# 06-Si5341_PLL.net
KiCad netlist of a schematic drawn in Altium Designer
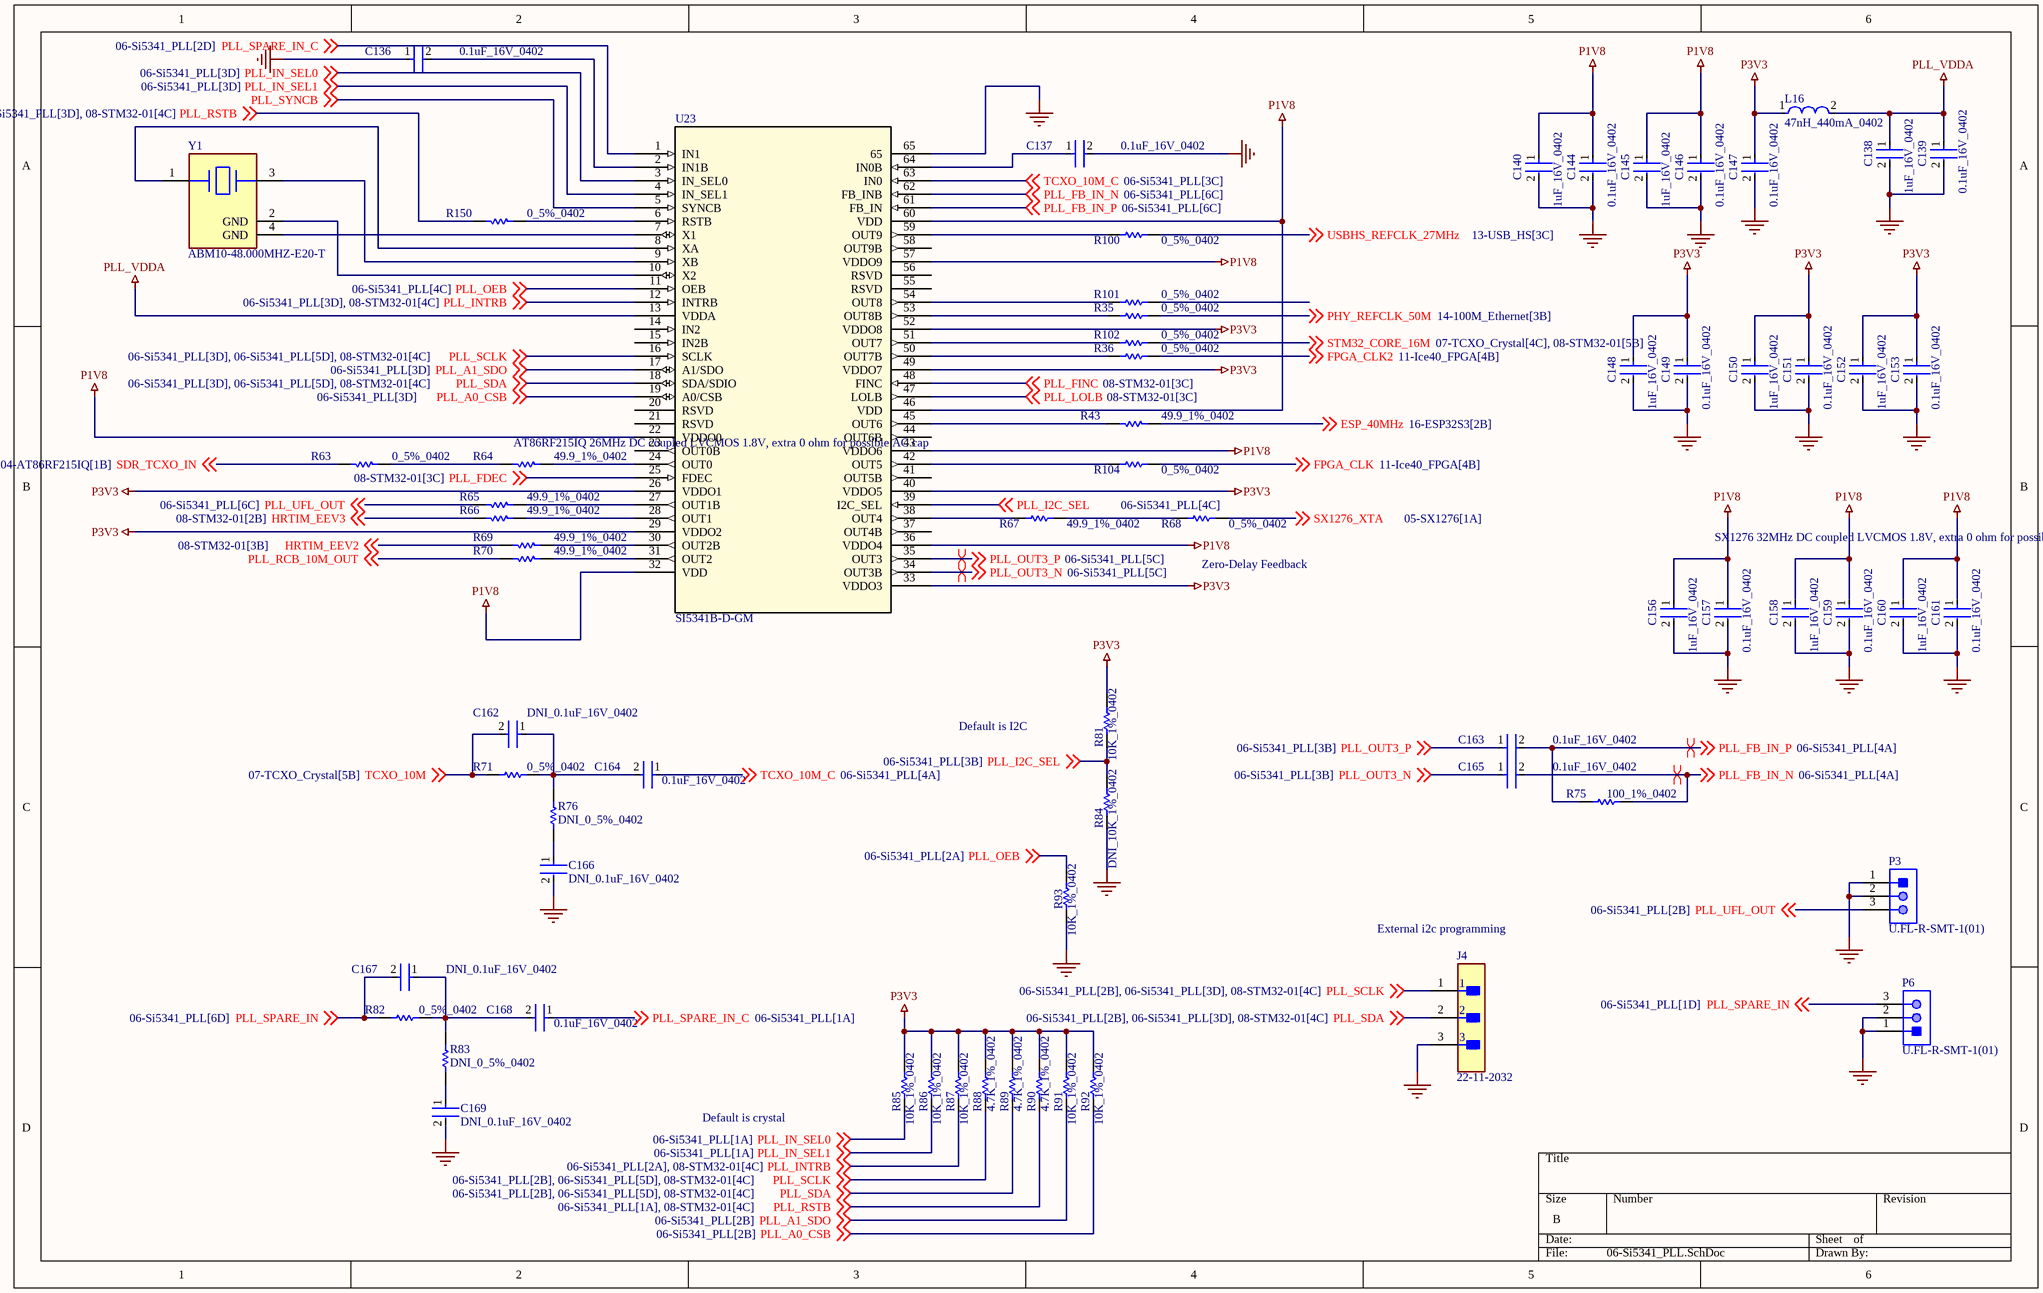
[diagram p0: 06-Si5341_PLL.SchDoc]

(export (version "E")
  (design (tool "Eeschema 10.0.6"))
  (components
    (comp (ref "C136")
      (value "0.1uF_16V_0402")
      (footprint "FP-C0402-BB-MFG")
      (description "CAP CER 0.1UF 16V 5% X7R 0402")
      (fields
        (field (name "MANUFACTURER") "Kemet")
        (field (name "MANUFACTURER PART NUMBER") "C0402C104J4RACTU")
      )
      (libsource (lib "Altium Content Vault") (part "b4654b650e69147ec39a6b967a45e02"))
    )
    (comp (ref "C137")
      (value "0.1uF_16V_0402")
      (footprint "FP-C0402-BB-MFG")
      (description "CAP CER 0.1UF 16V 5% X7R 0402")
      (fields
        (field (name "MANUFACTURER") "Kemet")
        (field (name "MANUFACTURER PART NUMBER") "C0402C104J4RACTU")
      )
      (libsource (lib "Altium Content Vault") (part "b4654b650e69147ec39a6b967a45e02"))
    )
    (comp (ref "C138")
      (value "1uF_16V_0402")
      (footprint "FP-0402-L_1_0_0_05-W_0_5-IPC_A")
      (description "None")
      (fields (field (name "TOLERANCE") "10%"))
      (libsource (lib "Altium Content Vault") (part "b4654b650e69147ec39a6b967a45e02"))
    )
    (comp (ref "C139")
      (value "0.1uF_16V_0402")
      (footprint "FP-C0402-BB-MFG")
      (description "CAP CER 0.1UF 16V 5% X7R 0402")
      (fields
        (field (name "MANUFACTURER") "Kemet")
        (field (name "MANUFACTURER PART NUMBER") "C0402C104J4RACTU")
      )
      (libsource (lib "Altium Content Vault") (part "b4654b650e69147ec39a6b967a45e02"))
    )
    (comp (ref "C140")
      (value "1uF_16V_0402")
      (footprint "FP-0402-L_1_0_0_05-W_0_5-IPC_A")
      (description "None")
      (fields (field (name "TOLERANCE") "10%"))
      (libsource (lib "Altium Content Vault") (part "b4654b650e69147ec39a6b967a45e02"))
    )
    (comp (ref "C144")
      (value "0.1uF_16V_0402")
      (footprint "FP-C0402-BB-MFG")
      (description "CAP CER 0.1UF 16V 5% X7R 0402")
      (fields
        (field (name "MANUFACTURER") "Kemet")
        (field (name "MANUFACTURER PART NUMBER") "C0402C104J4RACTU")
      )
      (libsource (lib "Altium Content Vault") (part "b4654b650e69147ec39a6b967a45e02"))
    )
    (comp (ref "C145")
      (value "1uF_16V_0402")
      (footprint "FP-0402-L_1_0_0_05-W_0_5-IPC_A")
      (description "None")
      (fields (field (name "TOLERANCE") "10%"))
      (libsource (lib "Altium Content Vault") (part "b4654b650e69147ec39a6b967a45e02"))
    )
    (comp (ref "C146")
      (value "0.1uF_16V_0402")
      (footprint "FP-C0402-BB-MFG")
      (description "CAP CER 0.1UF 16V 5% X7R 0402")
      (fields
        (field (name "MANUFACTURER") "Kemet")
        (field (name "MANUFACTURER PART NUMBER") "C0402C104J4RACTU")
      )
      (libsource (lib "Altium Content Vault") (part "b4654b650e69147ec39a6b967a45e02"))
    )
    (comp (ref "C147")
      (value "0.1uF_16V_0402")
      (footprint "FP-C0402-BB-MFG")
      (description "CAP CER 0.1UF 16V 5% X7R 0402")
      (fields
        (field (name "MANUFACTURER") "Kemet")
        (field (name "MANUFACTURER PART NUMBER") "C0402C104J4RACTU")
      )
      (libsource (lib "Altium Content Vault") (part "b4654b650e69147ec39a6b967a45e02"))
    )
    (comp (ref "C148")
      (value "1uF_16V_0402")
      (footprint "FP-0402-L_1_0_0_05-W_0_5-IPC_A")
      (description "None")
      (fields (field (name "TOLERANCE") "10%"))
      (libsource (lib "Altium Content Vault") (part "b4654b650e69147ec39a6b967a45e02"))
    )
    (comp (ref "C149")
      (value "0.1uF_16V_0402")
      (footprint "FP-C0402-BB-MFG")
      (description "CAP CER 0.1UF 16V 5% X7R 0402")
      (fields
        (field (name "MANUFACTURER") "Kemet")
        (field (name "MANUFACTURER PART NUMBER") "C0402C104J4RACTU")
      )
      (libsource (lib "Altium Content Vault") (part "b4654b650e69147ec39a6b967a45e02"))
    )
    (comp (ref "C150")
      (value "1uF_16V_0402")
      (footprint "FP-0402-L_1_0_0_05-W_0_5-IPC_A")
      (description "None")
      (fields (field (name "TOLERANCE") "10%"))
      (libsource (lib "Altium Content Vault") (part "b4654b650e69147ec39a6b967a45e02"))
    )
    (comp (ref "C151")
      (value "0.1uF_16V_0402")
      (footprint "FP-C0402-BB-MFG")
      (description "CAP CER 0.1UF 16V 5% X7R 0402")
      (fields
        (field (name "MANUFACTURER") "Kemet")
        (field (name "MANUFACTURER PART NUMBER") "C0402C104J4RACTU")
      )
      (libsource (lib "Altium Content Vault") (part "b4654b650e69147ec39a6b967a45e02"))
    )
    (comp (ref "C152")
      (value "1uF_16V_0402")
      (footprint "FP-0402-L_1_0_0_05-W_0_5-IPC_A")
      (description "None")
      (fields (field (name "TOLERANCE") "10%"))
      (libsource (lib "Altium Content Vault") (part "b4654b650e69147ec39a6b967a45e02"))
    )
    (comp (ref "C153")
      (value "0.1uF_16V_0402")
      (footprint "FP-C0402-BB-MFG")
      (description "CAP CER 0.1UF 16V 5% X7R 0402")
      (fields
        (field (name "MANUFACTURER") "Kemet")
        (field (name "MANUFACTURER PART NUMBER") "C0402C104J4RACTU")
      )
      (libsource (lib "Altium Content Vault") (part "b4654b650e69147ec39a6b967a45e02"))
    )
    (comp (ref "C156")
      (value "1uF_16V_0402")
      (footprint "FP-0402-L_1_0_0_05-W_0_5-IPC_A")
      (description "None")
      (fields (field (name "TOLERANCE") "10%"))
      (libsource (lib "Altium Content Vault") (part "b4654b650e69147ec39a6b967a45e02"))
    )
    (comp (ref "C157")
      (value "0.1uF_16V_0402")
      (footprint "FP-C0402-BB-MFG")
      (description "CAP CER 0.1UF 16V 5% X7R 0402")
      (fields
        (field (name "MANUFACTURER") "Kemet")
        (field (name "MANUFACTURER PART NUMBER") "C0402C104J4RACTU")
      )
      (libsource (lib "Altium Content Vault") (part "b4654b650e69147ec39a6b967a45e02"))
    )
    (comp (ref "C158")
      (value "1uF_16V_0402")
      (footprint "FP-0402-L_1_0_0_05-W_0_5-IPC_A")
      (description "None")
      (fields (field (name "TOLERANCE") "10%"))
      (libsource (lib "Altium Content Vault") (part "b4654b650e69147ec39a6b967a45e02"))
    )
    (comp (ref "C159")
      (value "0.1uF_16V_0402")
      (footprint "FP-C0402-BB-MFG")
      (description "CAP CER 0.1UF 16V 5% X7R 0402")
      (fields
        (field (name "MANUFACTURER") "Kemet")
        (field (name "MANUFACTURER PART NUMBER") "C0402C104J4RACTU")
      )
      (libsource (lib "Altium Content Vault") (part "b4654b650e69147ec39a6b967a45e02"))
    )
    (comp (ref "C160")
      (value "1uF_16V_0402")
      (footprint "FP-0402-L_1_0_0_05-W_0_5-IPC_A")
      (description "None")
      (fields (field (name "TOLERANCE") "10%"))
      (libsource (lib "Altium Content Vault") (part "b4654b650e69147ec39a6b967a45e02"))
    )
    (comp (ref "C161")
      (value "0.1uF_16V_0402")
      (footprint "FP-C0402-BB-MFG")
      (description "CAP CER 0.1UF 16V 5% X7R 0402")
      (fields
        (field (name "MANUFACTURER") "Kemet")
        (field (name "MANUFACTURER PART NUMBER") "C0402C104J4RACTU")
      )
      (libsource (lib "Altium Content Vault") (part "b4654b650e69147ec39a6b967a45e02"))
    )
    (comp (ref "C162")
      (value "DNI_0.1uF_16V_0402")
      (footprint "FP-C0402-BB-MFG")
      (description "CAP CER 0.1UF 16V 5% X7R 0402")
      (fields
        (field (name "MANUFACTURER") "Kemet")
        (field (name "MANUFACTURER PART NUMBER") "C0402C104J4RACTU")
      )
      (libsource (lib "Altium Content Vault") (part "b4654b650e69147ec39a6b967a45e02"))
    )
    (comp (ref "C163")
      (value "0.1uF_16V_0402")
      (footprint "FP-C0402-BB-MFG")
      (description "CAP CER 0.1UF 16V 5% X7R 0402")
      (fields
        (field (name "MANUFACTURER") "Kemet")
        (field (name "MANUFACTURER PART NUMBER") "C0402C104J4RACTU")
      )
      (libsource (lib "Altium Content Vault") (part "b4654b650e69147ec39a6b967a45e02"))
    )
    (comp (ref "C164")
      (value "0.1uF_16V_0402")
      (footprint "FP-C0402-BB-MFG")
      (description "CAP CER 0.1UF 16V 5% X7R 0402")
      (fields
        (field (name "MANUFACTURER") "Kemet")
        (field (name "MANUFACTURER PART NUMBER") "C0402C104J4RACTU")
      )
      (libsource (lib "Altium Content Vault") (part "b4654b650e69147ec39a6b967a45e02"))
    )
    (comp (ref "C165")
      (value "0.1uF_16V_0402")
      (footprint "FP-C0402-BB-MFG")
      (description "CAP CER 0.1UF 16V 5% X7R 0402")
      (fields
        (field (name "MANUFACTURER") "Kemet")
        (field (name "MANUFACTURER PART NUMBER") "C0402C104J4RACTU")
      )
      (libsource (lib "Altium Content Vault") (part "b4654b650e69147ec39a6b967a45e02"))
    )
    (comp (ref "C166")
      (value "DNI_0.1uF_16V_0402")
      (footprint "FP-C0402-BB-MFG")
      (description "CAP CER 0.1UF 16V 5% X7R 0402")
      (fields
        (field (name "MANUFACTURER") "Kemet")
        (field (name "MANUFACTURER PART NUMBER") "C0402C104J4RACTU")
      )
      (libsource (lib "Altium Content Vault") (part "b4654b650e69147ec39a6b967a45e02"))
    )
    (comp (ref "C167")
      (value "DNI_0.1uF_16V_0402")
      (footprint "FP-C0402-BB-MFG")
      (description "CAP CER 0.1UF 16V 5% X7R 0402")
      (fields
        (field (name "MANUFACTURER") "Kemet")
        (field (name "MANUFACTURER PART NUMBER") "C0402C104J4RACTU")
      )
      (libsource (lib "Altium Content Vault") (part "b4654b650e69147ec39a6b967a45e02"))
    )
    (comp (ref "C168")
      (value "0.1uF_16V_0402")
      (footprint "FP-C0402-BB-MFG")
      (description "CAP CER 0.1UF 16V 5% X7R 0402")
      (fields
        (field (name "MANUFACTURER") "Kemet")
        (field (name "MANUFACTURER PART NUMBER") "C0402C104J4RACTU")
      )
      (libsource (lib "Altium Content Vault") (part "b4654b650e69147ec39a6b967a45e02"))
    )
    (comp (ref "C169")
      (value "DNI_0.1uF_16V_0402")
      (footprint "FP-C0402-BB-MFG")
      (description "CAP CER 0.1UF 16V 5% X7R 0402")
      (fields
        (field (name "MANUFACTURER") "Kemet")
        (field (name "MANUFACTURER PART NUMBER") "C0402C104J4RACTU")
      )
      (libsource (lib "Altium Content Vault") (part "b4654b650e69147ec39a6b967a45e02"))
    )
    (comp (ref "J4")
      (value "22-11-2032")
      (footprint "FP-22-11-2032-MFG")
      (description "CONN HEADER VERT 3POS 2.54MM")
      (fields
        (field (name "MANUFACTURER") "Molex")
        (field (name "OCTOPART") "https://octopart.com/22-11-2032-molex-10085")
      )
      (libsource (lib "Altium Content Vault") (part "0d3f023dd272f625e17a2be33dea85f"))
    )
    (comp (ref "L16")
      (value "47nH_440mA_0402")
      (footprint "FP-LQW15AN_80-MFG")
      (description "Wire Wound RF Inductor 47nH ±5% 440mA 0.648Ω 0402 (1005)")
      (fields (field (name "TOLERANCE") "5%"))
      (libsource (lib "Altium Content Vault") (part "725321dda6339637d4d059423bc1c3c"))
    )
    (comp (ref "P3")
      (value "U.FL-R-SMT-1(01)")
      (footprint "HRS-U.FL-R-SMT-3_V")
      (description "Ultra Small Coaxial Connector, 6 GHz, -40 to 90 degC, 3-Pin SMD, RoHS, Bulk")
      (fields (field (name "MANUFACTURER") "Hirose Electric"))
      (libsource (lib "") (part "CN-1P-M-R3_1"))
    )
    (comp (ref "P6")
      (value "U.FL-R-SMT-1(01)")
      (footprint "HRS-U.FL-R-SMT-3_V")
      (description "Ultra Small Coaxial Connector, 6 GHz, -40 to 90 degC, 3-Pin SMD, RoHS, Bulk")
      (fields (field (name "MANUFACTURER") "Hirose Electric"))
      (libsource (lib "Altium Content Vault") (part "CN-1P-M-R3"))
    )
    (comp (ref "R35")
      (value "0_5%_0402")
      (footprint "RESC1005X40X25NL05T10")
      (fields (field (name "MANUFACTURER") "Panasonic") (field (name "PART NUMBER") "ERJ-U020R00X"))
      (libsource (lib "Altium Content Vault") (part "RES"))
    )
    (comp (ref "R36")
      (value "0_5%_0402")
      (footprint "RESC1005X40X25NL05T10")
      (fields (field (name "MANUFACTURER") "Panasonic") (field (name "PART NUMBER") "ERJ-U020R00X"))
      (libsource (lib "Altium Content Vault") (part "RES"))
    )
    (comp (ref "R43")
      (value "49.9_1%_0402")
      (footprint "RESC1005X40X25NL10T10")
      (fields (field (name "PART NUMBER") "RK73H1ETTP49R9F") (field (name "MANUFACTURER") "KOA Speer"))
      (libsource (lib "Altium Content Vault") (part "RES"))
    )
    (comp (ref "R63")
      (value "0_5%_0402")
      (footprint "RESC1005X40X25NL05T10")
      (fields (field (name "MANUFACTURER") "Panasonic") (field (name "PART NUMBER") "ERJ-U020R00X"))
      (libsource (lib "Altium Content Vault") (part "RES"))
    )
    (comp (ref "R64")
      (value "49.9_1%_0402")
      (footprint "RESC1005X40X25NL10T10")
      (fields (field (name "PART NUMBER") "RK73H1ETTP49R9F") (field (name "MANUFACTURER") "KOA Speer"))
      (libsource (lib "Altium Content Vault") (part "RES"))
    )
    (comp (ref "R65")
      (value "49.9_1%_0402")
      (footprint "RESC1005X40X25NL10T10")
      (fields (field (name "PART NUMBER") "RK73H1ETTP49R9F") (field (name "MANUFACTURER") "KOA Speer"))
      (libsource (lib "Altium Content Vault") (part "RES"))
    )
    (comp (ref "R66")
      (value "49.9_1%_0402")
      (footprint "RESC1005X40X25NL10T10")
      (fields (field (name "PART NUMBER") "RK73H1ETTP49R9F") (field (name "MANUFACTURER") "KOA Speer"))
      (libsource (lib "Altium Content Vault") (part "RES"))
    )
    (comp (ref "R67")
      (value "49.9_1%_0402")
      (footprint "RESC1005X40X25NL10T10")
      (fields (field (name "PART NUMBER") "RK73H1ETTP49R9F") (field (name "MANUFACTURER") "KOA Speer"))
      (libsource (lib "Altium Content Vault") (part "RES"))
    )
    (comp (ref "R68")
      (value "0_5%_0402")
      (footprint "RESC1005X40X25NL05T10")
      (fields (field (name "MANUFACTURER") "Panasonic") (field (name "PART NUMBER") "ERJ-U020R00X"))
      (libsource (lib "Altium Content Vault") (part "RES"))
    )
    (comp (ref "R69")
      (value "49.9_1%_0402")
      (footprint "RESC1005X40X25NL10T10")
      (fields (field (name "PART NUMBER") "RK73H1ETTP49R9F") (field (name "MANUFACTURER") "KOA Speer"))
      (libsource (lib "Altium Content Vault") (part "RES"))
    )
    (comp (ref "R70")
      (value "49.9_1%_0402")
      (footprint "RESC1005X40X25NL10T10")
      (fields (field (name "PART NUMBER") "RK73H1ETTP49R9F") (field (name "MANUFACTURER") "KOA Speer"))
      (libsource (lib "Altium Content Vault") (part "RES"))
    )
    (comp (ref "R71")
      (value "0_5%_0402")
      (footprint "RESC1005X40X25NL05T10")
      (fields (field (name "MANUFACTURER") "Panasonic") (field (name "PART NUMBER") "ERJ-U020R00X"))
      (libsource (lib "Altium Content Vault") (part "RES"))
    )
    (comp (ref "R75")
      (value "100_1%_0402")
      (footprint "RESC1005X40X25NL05T10")
      (fields (field (name "MANUFACTURER") "Yageo") (field (name "PART NUMBER") "RC0402FR-13100RL"))
      (libsource (lib "Altium Content Vault") (part "RES"))
    )
    (comp (ref "R76")
      (value "DNI_0_5%_0402")
      (footprint "RESC1005X40X25NL05T10")
      (fields (field (name "MANUFACTURER") "Panasonic") (field (name "PART NUMBER") "ERJ-U020R00X"))
      (libsource (lib "Altium Content Vault") (part "RES"))
    )
    (comp (ref "R81")
      (value "10K_1%_0402")
      (footprint "RESC1005X40X25NL10T10")
      (fields (field (name "MANUFACTURER") "Bourns") (field (name "PART NUMBER") "CR0402-FX-1002GLF"))
      (libsource (lib "Altium Content Vault") (part "RES"))
    )
    (comp (ref "R82")
      (value "0_5%_0402")
      (footprint "RESC1005X40X25NL05T10")
      (fields (field (name "MANUFACTURER") "Panasonic") (field (name "PART NUMBER") "ERJ-U020R00X"))
      (libsource (lib "Altium Content Vault") (part "RES"))
    )
    (comp (ref "R83")
      (value "DNI_0_5%_0402")
      (footprint "RESC1005X40X25NL05T10")
      (fields (field (name "MANUFACTURER") "Panasonic") (field (name "PART NUMBER") "ERJ-U020R00X"))
      (libsource (lib "Altium Content Vault") (part "RES"))
    )
    (comp (ref "R84")
      (value "DNI_10K_1%_0402")
      (footprint "RESC1005X40X25NL10T10")
      (fields (field (name "MANUFACTURER") "Bourns") (field (name "PART NUMBER") "CR0402-FX-1002GLF"))
      (libsource (lib "Altium Content Vault") (part "RES"))
    )
    (comp (ref "R85")
      (value "10K_1%_0402")
      (footprint "RESC1005X40X25NL10T10")
      (fields (field (name "MANUFACTURER") "Bourns") (field (name "PART NUMBER") "CR0402-FX-1002GLF"))
      (libsource (lib "Altium Content Vault") (part "RES"))
    )
    (comp (ref "R86")
      (value "10K_1%_0402")
      (footprint "RESC1005X40X25NL10T10")
      (fields (field (name "MANUFACTURER") "Bourns") (field (name "PART NUMBER") "CR0402-FX-1002GLF"))
      (libsource (lib "Altium Content Vault") (part "RES"))
    )
    (comp (ref "R87")
      (value "10K_1%_0402")
      (footprint "RESC1005X40X25NL10T10")
      (fields (field (name "MANUFACTURER") "Bourns") (field (name "PART NUMBER") "CR0402-FX-1002GLF"))
      (libsource (lib "Altium Content Vault") (part "RES"))
    )
    (comp (ref "R88")
      (value "4.7K_1%_0402")
      (footprint "RESC1005X40X25NL10T10")
      (fields (field (name "MANUFACTURER") "Bourns") (field (name "PART NUMBER") "CR0402-FX-4701GLF"))
      (libsource (lib "Altium Content Vault") (part "RES"))
    )
    (comp (ref "R89")
      (value "4.7K_1%_0402")
      (footprint "RESC1005X40X25NL10T10")
      (fields (field (name "MANUFACTURER") "Bourns") (field (name "PART NUMBER") "CR0402-FX-4701GLF"))
      (libsource (lib "Altium Content Vault") (part "RES"))
    )
    (comp (ref "R90")
      (value "4.7K_1%_0402")
      (footprint "RESC1005X40X25NL10T10")
      (fields (field (name "MANUFACTURER") "Bourns") (field (name "PART NUMBER") "CR0402-FX-4701GLF"))
      (libsource (lib "Altium Content Vault") (part "RES"))
    )
    (comp (ref "R91")
      (value "10K_1%_0402")
      (footprint "RESC1005X40X25NL10T10")
      (fields (field (name "MANUFACTURER") "Bourns") (field (name "PART NUMBER") "CR0402-FX-1002GLF"))
      (libsource (lib "Altium Content Vault") (part "RES"))
    )
    (comp (ref "R92")
      (value "10K_1%_0402")
      (footprint "RESC1005X40X25NL10T10")
      (fields (field (name "MANUFACTURER") "Bourns") (field (name "PART NUMBER") "CR0402-FX-1002GLF"))
      (libsource (lib "Altium Content Vault") (part "RES"))
    )
    (comp (ref "R93")
      (value "10K_1%_0402")
      (footprint "RESC1005X40X25NL10T10")
      (fields (field (name "MANUFACTURER") "Bourns") (field (name "PART NUMBER") "CR0402-FX-1002GLF"))
      (libsource (lib "Altium Content Vault") (part "RES"))
    )
    (comp (ref "R100")
      (value "0_5%_0402")
      (footprint "RESC1005X40X25NL05T10")
      (fields (field (name "MANUFACTURER") "Panasonic") (field (name "PART NUMBER") "ERJ-U020R00X"))
      (libsource (lib "Altium Content Vault") (part "RES"))
    )
    (comp (ref "R101")
      (value "0_5%_0402")
      (footprint "RESC1005X40X25NL05T10")
      (fields (field (name "MANUFACTURER") "Panasonic") (field (name "PART NUMBER") "ERJ-U020R00X"))
      (libsource (lib "Altium Content Vault") (part "RES"))
    )
    (comp (ref "R102")
      (value "0_5%_0402")
      (footprint "RESC1005X40X25NL05T10")
      (fields (field (name "MANUFACTURER") "Panasonic") (field (name "PART NUMBER") "ERJ-U020R00X"))
      (libsource (lib "Altium Content Vault") (part "RES"))
    )
    (comp (ref "R104")
      (value "0_5%_0402")
      (footprint "RESC1005X40X25NL05T10")
      (fields (field (name "MANUFACTURER") "Panasonic") (field (name "PART NUMBER") "ERJ-U020R00X"))
      (libsource (lib "Altium Content Vault") (part "RES"))
    )
    (comp (ref "R150")
      (value "0_5%_0402")
      (footprint "RESC1005X40X25NL05T10")
      (fields (field (name "MANUFACTURER") "Panasonic") (field (name "PART NUMBER") "ERJ-U020R00X"))
      (libsource (lib "Altium Content Vault") (part "RES"))
    )
    (comp (ref "U23")
      (value "SI5341B-D-GM")
      (footprint "QFN64_SI5341_SIL_SKY")
      (description "No Description Available")
      (fields
        (field (name "MANUFACTURER_PART_NUMBER") "SI5341B-B05071-GM")
        (field (name "COPYRIGHT") "Copyright (C) 2023 Ultra Librarian. All rights reserved.")
      )
      (libsource (lib "SI5341B-B05071-GM") (part "SI5341B-B05071-GM"))
    )
    (comp (ref "Y1")
      (value "ABM10-48.000MHZ-E20-T")
      (footprint "FP-ABM10-MFG")
      (description "Crystal 48MHz ±20ppm 10pF SMD-4 2.5mm x 2mm")
      (fields (field (name "TOLERANCE") "20ppm"))
      (libsource (lib "Altium Content Vault") (part "0934ba461506c7e3a0bb4df7a4ed385"))
    )
  )
  (nets
    (net (code "1") (name "ESP_40MHz") (class "Default")
      (node (ref "R43") (pin "2") (pinfunction "2_2") (pintype "passive"))
    )
    (net (code "2") (name "FPGA_CLK") (class "Default")
      (node (ref "R104") (pin "2") (pinfunction "2_2") (pintype "passive"))
    )
    (net (code "3") (name "FPGA_CLK2") (class "Default")
      (node (ref "R36") (pin "2") (pinfunction "2_2") (pintype "passive"))
    )
    (net (code "4") (name "GND") (class "Default")
      (node (ref "C136") (pin "1") (pinfunction "1_1") (pintype "passive"))
      (node (ref "C137") (pin "2") (pinfunction "2_2") (pintype "passive"))
      (node (ref "C138") (pin "2") (pinfunction "2_2") (pintype "passive"))
      (node (ref "C139") (pin "2") (pinfunction "2_2") (pintype "passive"))
      (node (ref "C140") (pin "2") (pinfunction "2_2") (pintype "passive"))
      (node (ref "C144") (pin "2") (pinfunction "2_2") (pintype "passive"))
      (node (ref "C145") (pin "2") (pinfunction "2_2") (pintype "passive"))
      (node (ref "C146") (pin "2") (pinfunction "2_2") (pintype "passive"))
      (node (ref "C147") (pin "2") (pinfunction "2_2") (pintype "passive"))
      (node (ref "C148") (pin "2") (pinfunction "2_2") (pintype "passive"))
      (node (ref "C149") (pin "2") (pinfunction "2_2") (pintype "passive"))
      (node (ref "C150") (pin "2") (pinfunction "2_2") (pintype "passive"))
      (node (ref "C151") (pin "2") (pinfunction "2_2") (pintype "passive"))
      (node (ref "C152") (pin "2") (pinfunction "2_2") (pintype "passive"))
      (node (ref "C153") (pin "2") (pinfunction "2_2") (pintype "passive"))
      (node (ref "C156") (pin "2") (pinfunction "2_2") (pintype "passive"))
      (node (ref "C157") (pin "2") (pinfunction "2_2") (pintype "passive"))
      (node (ref "C158") (pin "2") (pinfunction "2_2") (pintype "passive"))
      (node (ref "C159") (pin "2") (pinfunction "2_2") (pintype "passive"))
      (node (ref "C160") (pin "2") (pinfunction "2_2") (pintype "passive"))
      (node (ref "C161") (pin "2") (pinfunction "2_2") (pintype "passive"))
      (node (ref "C166") (pin "2") (pinfunction "2_2") (pintype "passive"))
      (node (ref "C169") (pin "2") (pinfunction "2_2") (pintype "passive"))
      (node (ref "J4") (pin "3") (pinfunction "3_3") (pintype "passive"))
      (node (ref "P3") (pin "1") (pinfunction "1_1") (pintype "passive"))
      (node (ref "P3") (pin "2") (pinfunction "2_2") (pintype "passive"))
      (node (ref "P6") (pin "1") (pinfunction "1_1") (pintype "passive"))
      (node (ref "P6") (pin "2") (pinfunction "2_2") (pintype "passive"))
      (node (ref "R84") (pin "1") (pinfunction "1_1") (pintype "passive"))
      (node (ref "R93") (pin "1") (pinfunction "1_1") (pintype "passive"))
      (node (ref "U23") (pin "65") (pinfunction "65_65") (pintype "passive"))
    )
    (net (code "5") (name "HRTIM_EEV2") (class "Default")
      (node (ref "R69") (pin "1") (pinfunction "1_1") (pintype "passive"))
    )
    (net (code "6") (name "HRTIM_EEV3") (class "Default")
      (node (ref "R66") (pin "1") (pinfunction "1_1") (pintype "passive"))
    )
    (net (code "7") (name "Net-(C162-Pad1)") (class "Default")
      (node (ref "C162") (pin "1") (pinfunction "1_1") (pintype "passive"))
      (node (ref "C164") (pin "2") (pinfunction "2_2") (pintype "passive"))
      (node (ref "R71") (pin "2") (pinfunction "2_2") (pintype "passive"))
      (node (ref "R76") (pin "2") (pinfunction "2_2") (pintype "passive"))
    )
    (net (code "8") (name "Net-(C166-Pad1)") (class "Default")
      (node (ref "C166") (pin "1") (pinfunction "1_1") (pintype "passive"))
      (node (ref "R76") (pin "1") (pinfunction "1_1") (pintype "passive"))
    )
    (net (code "9") (name "Net-(C167-Pad1)") (class "Default")
      (node (ref "C167") (pin "1") (pinfunction "1_1") (pintype "passive"))
      (node (ref "C168") (pin "2") (pinfunction "2_2") (pintype "passive"))
      (node (ref "R82") (pin "2") (pinfunction "2_2") (pintype "passive"))
      (node (ref "R83") (pin "2") (pinfunction "2_2") (pintype "passive"))
    )
    (net (code "10") (name "Net-(C169-Pad1)") (class "Default")
      (node (ref "C169") (pin "1") (pinfunction "1_1") (pintype "passive"))
      (node (ref "R83") (pin "1") (pinfunction "1_1") (pintype "passive"))
    )
    (net (code "11") (name "Net-(R63-Pad1)") (class "Default")
      (node (ref "R63") (pin "1") (pinfunction "1_1") (pintype "passive"))
      (node (ref "R64") (pin "1") (pinfunction "1_1") (pintype "passive"))
    )
    (net (code "12") (name "Net-(R67-Pad1)") (class "Default")
      (node (ref "R67") (pin "1") (pinfunction "1_1") (pintype "passive"))
      (node (ref "R68") (pin "1") (pinfunction "1_1") (pintype "passive"))
    )
    (net (code "13") (name "Net-(U23-IN0B)") (class "Default")
      (node (ref "C137") (pin "1") (pinfunction "1_1") (pintype "passive"))
      (node (ref "U23") (pin "64") (pinfunction "IN0B_64") (pintype "input"))
    )
    (net (code "14") (name "Net-(U23-IN1B)") (class "Default")
      (node (ref "C136") (pin "2") (pinfunction "2_2") (pintype "passive"))
      (node (ref "U23") (pin "2") (pinfunction "IN1B_2") (pintype "input"))
    )
    (net (code "15") (name "Net-(U23-OUT0)") (class "Default")
      (node (ref "R64") (pin "2") (pinfunction "2_2") (pintype "passive"))
      (node (ref "U23") (pin "24") (pinfunction "OUT0_24") (pintype "output"))
    )
    (net (code "16") (name "Net-(U23-OUT1)") (class "Default")
      (node (ref "R66") (pin "2") (pinfunction "2_2") (pintype "passive"))
      (node (ref "U23") (pin "28") (pinfunction "OUT1_28") (pintype "output"))
    )
    (net (code "17") (name "Net-(U23-OUT1B)") (class "Default")
      (node (ref "R65") (pin "2") (pinfunction "2_2") (pintype "passive"))
      (node (ref "U23") (pin "27") (pinfunction "OUT1B_27") (pintype "output"))
    )
    (net (code "18") (name "Net-(U23-OUT2)") (class "Default")
      (node (ref "R70") (pin "2") (pinfunction "2_2") (pintype "passive"))
      (node (ref "U23") (pin "31") (pinfunction "OUT2_31") (pintype "output"))
    )
    (net (code "19") (name "Net-(U23-OUT2B)") (class "Default")
      (node (ref "R69") (pin "2") (pinfunction "2_2") (pintype "passive"))
      (node (ref "U23") (pin "30") (pinfunction "OUT2B_30") (pintype "output"))
    )
    (net (code "20") (name "Net-(U23-OUT4)") (class "Default")
      (node (ref "R67") (pin "2") (pinfunction "2_2") (pintype "passive"))
      (node (ref "U23") (pin "38") (pinfunction "OUT4_38") (pintype "output"))
    )
    (net (code "21") (name "Net-(U23-OUT5)") (class "Default")
      (node (ref "R104") (pin "1") (pinfunction "1_1") (pintype "passive"))
      (node (ref "U23") (pin "42") (pinfunction "OUT5_42") (pintype "output"))
    )
    (net (code "22") (name "Net-(U23-OUT6)") (class "Default")
      (node (ref "R43") (pin "1") (pinfunction "1_1") (pintype "passive"))
      (node (ref "U23") (pin "45") (pinfunction "OUT6_45") (pintype "output"))
    )
    (net (code "23") (name "Net-(U23-OUT7)") (class "Default")
      (node (ref "R102") (pin "1") (pinfunction "1_1") (pintype "passive"))
      (node (ref "U23") (pin "51") (pinfunction "OUT7_51") (pintype "output"))
    )
    (net (code "24") (name "Net-(U23-OUT7B)") (class "Default")
      (node (ref "R36") (pin "1") (pinfunction "1_1") (pintype "passive"))
      (node (ref "U23") (pin "50") (pinfunction "OUT7B_50") (pintype "output"))
    )
    (net (code "25") (name "Net-(U23-OUT8)") (class "Default")
      (node (ref "R101") (pin "1") (pinfunction "1_1") (pintype "passive"))
      (node (ref "U23") (pin "54") (pinfunction "OUT8_54") (pintype "output"))
    )
    (net (code "26") (name "Net-(U23-OUT8B)") (class "Default")
      (node (ref "R35") (pin "1") (pinfunction "1_1") (pintype "passive"))
      (node (ref "U23") (pin "53") (pinfunction "OUT8B_53") (pintype "output"))
    )
    (net (code "27") (name "Net-(U23-OUT9)") (class "Default")
      (node (ref "R100") (pin "1") (pinfunction "1_1") (pintype "passive"))
      (node (ref "U23") (pin "59") (pinfunction "OUT9_59") (pintype "output"))
    )
    (net (code "28") (name "Net-(U23-RSTB)") (class "Default")
      (node (ref "R150") (pin "1") (pinfunction "1_1") (pintype "passive"))
      (node (ref "U23") (pin "6") (pinfunction "RSTB_6") (pintype "input"))
    )
    (net (code "29") (name "Net-(U23-X1)") (class "Default")
      (node (ref "U23") (pin "7") (pinfunction "X1_7") (pintype "bidirectional"))
      (node (ref "Y1") (pin "4") (pinfunction "GND_4") (pintype "power_in"))
    )
    (net (code "30") (name "Net-(U23-X2)") (class "Default")
      (node (ref "U23") (pin "10") (pinfunction "X2_10") (pintype "bidirectional"))
      (node (ref "Y1") (pin "2") (pinfunction "GND_2") (pintype "power_in"))
    )
    (net (code "31") (name "Net-(U23-XA)") (class "Default")
      (node (ref "U23") (pin "8") (pinfunction "XA_8") (pintype "input"))
      (node (ref "Y1") (pin "1") (pinfunction "1_1") (pintype "passive"))
    )
    (net (code "32") (name "Net-(U23-XB)") (class "Default")
      (node (ref "U23") (pin "9") (pinfunction "XB_9") (pintype "input"))
      (node (ref "Y1") (pin "3") (pinfunction "3_3") (pintype "passive"))
    )
    (net (code "33") (name "P1V8") (class "Default")
      (node (ref "C140") (pin "1") (pinfunction "1_1") (pintype "passive"))
      (node (ref "C144") (pin "1") (pinfunction "1_1") (pintype "passive"))
      (node (ref "C145") (pin "1") (pinfunction "1_1") (pintype "passive"))
      (node (ref "C146") (pin "1") (pinfunction "1_1") (pintype "passive"))
      (node (ref "C156") (pin "1") (pinfunction "1_1") (pintype "passive"))
      (node (ref "C157") (pin "1") (pinfunction "1_1") (pintype "passive"))
      (node (ref "C158") (pin "1") (pinfunction "1_1") (pintype "passive"))
      (node (ref "C159") (pin "1") (pinfunction "1_1") (pintype "passive"))
      (node (ref "C160") (pin "1") (pinfunction "1_1") (pintype "passive"))
      (node (ref "C161") (pin "1") (pinfunction "1_1") (pintype "passive"))
      (node (ref "U23") (pin "22") (pinfunction "VDDO0_22") (pintype "power_in"))
      (node (ref "U23") (pin "32") (pinfunction "VDD_32") (pintype "power_in"))
      (node (ref "U23") (pin "36") (pinfunction "VDDO4_36") (pintype "power_in"))
      (node (ref "U23") (pin "43") (pinfunction "VDDO6_43") (pintype "power_in"))
      (node (ref "U23") (pin "46") (pinfunction "VDD_46") (pintype "power_in"))
      (node (ref "U23") (pin "57") (pinfunction "VDDO9_57") (pintype "power_in"))
      (node (ref "U23") (pin "60") (pinfunction "VDD_60") (pintype "power_in"))
    )
    (net (code "34") (name "P3V3") (class "Default")
      (node (ref "C147") (pin "1") (pinfunction "1_1") (pintype "passive"))
      (node (ref "C148") (pin "1") (pinfunction "1_1") (pintype "passive"))
      (node (ref "C149") (pin "1") (pinfunction "1_1") (pintype "passive"))
      (node (ref "C150") (pin "1") (pinfunction "1_1") (pintype "passive"))
      (node (ref "C151") (pin "1") (pinfunction "1_1") (pintype "passive"))
      (node (ref "C152") (pin "1") (pinfunction "1_1") (pintype "passive"))
      (node (ref "C153") (pin "1") (pinfunction "1_1") (pintype "passive"))
      (node (ref "L16") (pin "1") (pinfunction "1_1") (pintype "passive"))
      (node (ref "R81") (pin "2") (pinfunction "2_2") (pintype "passive"))
      (node (ref "R85") (pin "2") (pinfunction "2_2") (pintype "passive"))
      (node (ref "R86") (pin "2") (pinfunction "2_2") (pintype "passive"))
      (node (ref "R87") (pin "2") (pinfunction "2_2") (pintype "passive"))
      (node (ref "R88") (pin "2") (pinfunction "2_2") (pintype "passive"))
      (node (ref "R89") (pin "2") (pinfunction "2_2") (pintype "passive"))
      (node (ref "R90") (pin "2") (pinfunction "2_2") (pintype "passive"))
      (node (ref "R91") (pin "2") (pinfunction "2_2") (pintype "passive"))
      (node (ref "R92") (pin "2") (pinfunction "2_2") (pintype "passive"))
      (node (ref "U23") (pin "26") (pinfunction "VDDO1_26") (pintype "power_in"))
      (node (ref "U23") (pin "29") (pinfunction "VDDO2_29") (pintype "power_in"))
      (node (ref "U23") (pin "33") (pinfunction "VDDO3_33") (pintype "power_in"))
      (node (ref "U23") (pin "40") (pinfunction "VDDO5_40") (pintype "power_in"))
      (node (ref "U23") (pin "49") (pinfunction "VDDO7_49") (pintype "power_in"))
      (node (ref "U23") (pin "52") (pinfunction "VDDO8_52") (pintype "power_in"))
    )
    (net (code "35") (name "PHY_REFCLK_50M") (class "Default")
      (node (ref "R35") (pin "2") (pinfunction "2_2") (pintype "passive"))
    )
    (net (code "36") (name "PLL_A0_CSB") (class "Default")
      (node (ref "R92") (pin "1") (pinfunction "1_1") (pintype "passive"))
      (node (ref "U23") (pin "19") (pinfunction "A0/CSB_19") (pintype "bidirectional"))
    )
    (net (code "37") (name "PLL_A1_SDO") (class "Default")
      (node (ref "R91") (pin "1") (pinfunction "1_1") (pintype "passive"))
      (node (ref "U23") (pin "17") (pinfunction "A1/SDO_17") (pintype "bidirectional"))
    )
    (net (code "38") (name "PLL_FB_IN_N") (class "Default")
      (node (ref "C165") (pin "2") (pinfunction "2_2") (pintype "passive"))
      (node (ref "R75") (pin "2") (pinfunction "2_2") (pintype "passive"))
      (node (ref "U23") (pin "62") (pinfunction "FB_INB_62") (pintype "input"))
    )
    (net (code "39") (name "PLL_FB_IN_P") (class "Default")
      (node (ref "C163") (pin "2") (pinfunction "2_2") (pintype "passive"))
      (node (ref "R75") (pin "1") (pinfunction "1_1") (pintype "passive"))
      (node (ref "U23") (pin "61") (pinfunction "FB_IN_61") (pintype "input"))
    )
    (net (code "40") (name "PLL_FDEC") (class "Default")
      (node (ref "U23") (pin "25") (pinfunction "FDEC_25") (pintype "input"))
    )
    (net (code "41") (name "PLL_FINC") (class "Default")
      (node (ref "U23") (pin "48") (pinfunction "FINC_48") (pintype "input"))
    )
    (net (code "42") (name "PLL_I2C_SEL") (class "Default")
      (node (ref "R81") (pin "1") (pinfunction "1_1") (pintype "passive"))
      (node (ref "R84") (pin "2") (pinfunction "2_2") (pintype "passive"))
      (node (ref "U23") (pin "39") (pinfunction "I2C_SEL_39") (pintype "input"))
    )
    (net (code "43") (name "PLL_INTRB") (class "Default")
      (node (ref "R87") (pin "1") (pinfunction "1_1") (pintype "passive"))
      (node (ref "U23") (pin "12") (pinfunction "INTRB_12") (pintype "input"))
    )
    (net (code "44") (name "PLL_IN_SEL0") (class "Default")
      (node (ref "R85") (pin "1") (pinfunction "1_1") (pintype "passive"))
      (node (ref "U23") (pin "3") (pinfunction "IN_SEL0_3") (pintype "input"))
    )
    (net (code "45") (name "PLL_IN_SEL1") (class "Default")
      (node (ref "R86") (pin "1") (pinfunction "1_1") (pintype "passive"))
      (node (ref "U23") (pin "4") (pinfunction "IN_SEL1_4") (pintype "input"))
    )
    (net (code "46") (name "PLL_LOLB") (class "Default")
      (node (ref "U23") (pin "47") (pinfunction "LOLB_47") (pintype "output"))
    )
    (net (code "47") (name "PLL_OEB") (class "Default")
      (node (ref "R93") (pin "2") (pinfunction "2_2") (pintype "passive"))
      (node (ref "U23") (pin "11") (pinfunction "OEB_11") (pintype "input"))
    )
    (net (code "48") (name "PLL_OUT3_N") (class "Default")
      (node (ref "C165") (pin "1") (pinfunction "1_1") (pintype "passive"))
      (node (ref "U23") (pin "34") (pinfunction "OUT3B_34") (pintype "output"))
    )
    (net (code "49") (name "PLL_OUT3_P") (class "Default")
      (node (ref "C163") (pin "1") (pinfunction "1_1") (pintype "passive"))
      (node (ref "U23") (pin "35") (pinfunction "OUT3_35") (pintype "output"))
    )
    (net (code "50") (name "PLL_RCB_10M_OUT") (class "Default")
      (node (ref "R70") (pin "1") (pinfunction "1_1") (pintype "passive"))
    )
    (net (code "51") (name "PLL_RSTB") (class "Default")
      (node (ref "R150") (pin "2") (pinfunction "2_2") (pintype "passive"))
      (node (ref "R90") (pin "1") (pinfunction "1_1") (pintype "passive"))
    )
    (net (code "52") (name "PLL_SCLK") (class "Default")
      (node (ref "J4") (pin "1") (pinfunction "1_1") (pintype "passive"))
      (node (ref "R88") (pin "1") (pinfunction "1_1") (pintype "passive"))
      (node (ref "U23") (pin "16") (pinfunction "SCLK_16") (pintype "input"))
    )
    (net (code "53") (name "PLL_SDA") (class "Default")
      (node (ref "J4") (pin "2") (pinfunction "2_2") (pintype "passive"))
      (node (ref "R89") (pin "1") (pinfunction "1_1") (pintype "passive"))
      (node (ref "U23") (pin "18") (pinfunction "SDA/SDIO_18") (pintype "bidirectional"))
    )
    (net (code "54") (name "PLL_SPARE_IN") (class "Default")
      (node (ref "C167") (pin "2") (pinfunction "2_2") (pintype "passive"))
      (node (ref "P6") (pin "3") (pinfunction "3_3") (pintype "passive"))
      (node (ref "R82") (pin "1") (pinfunction "1_1") (pintype "passive"))
    )
    (net (code "55") (name "PLL_SPARE_IN_C") (class "Default")
      (node (ref "C168") (pin "1") (pinfunction "1_1") (pintype "passive"))
      (node (ref "U23") (pin "1") (pinfunction "IN1_1") (pintype "input"))
    )
    (net (code "56") (name "PLL_SYNCB") (class "Default")
      (node (ref "U23") (pin "5") (pinfunction "SYNCB_5") (pintype "input"))
    )
    (net (code "57") (name "PLL_UFL_OUT") (class "Default")
      (node (ref "P3") (pin "3") (pinfunction "3_3") (pintype "passive"))
      (node (ref "R65") (pin "1") (pinfunction "1_1") (pintype "passive"))
    )
    (net (code "58") (name "PLL_VDDA") (class "Default")
      (node (ref "C138") (pin "1") (pinfunction "1_1") (pintype "passive"))
      (node (ref "C139") (pin "1") (pinfunction "1_1") (pintype "passive"))
      (node (ref "L16") (pin "2") (pinfunction "2_2") (pintype "passive"))
      (node (ref "U23") (pin "13") (pinfunction "VDDA_13") (pintype "power_in"))
    )
    (net (code "59") (name "SDR_TCXO_IN") (class "Default")
      (node (ref "R63") (pin "2") (pinfunction "2_2") (pintype "passive"))
    )
    (net (code "60") (name "STM32_CORE_16M") (class "Default")
      (node (ref "R102") (pin "2") (pinfunction "2_2") (pintype "passive"))
    )
    (net (code "61") (name "SX1276_XTA") (class "Default")
      (node (ref "R68") (pin "2") (pinfunction "2_2") (pintype "passive"))
    )
    (net (code "62") (name "TCXO_10M") (class "Default")
      (node (ref "C162") (pin "2") (pinfunction "2_2") (pintype "passive"))
      (node (ref "R71") (pin "1") (pinfunction "1_1") (pintype "passive"))
    )
    (net (code "63") (name "TCXO_10M_C") (class "Default")
      (node (ref "C164") (pin "1") (pinfunction "1_1") (pintype "passive"))
      (node (ref "U23") (pin "63") (pinfunction "IN0_63") (pintype "input"))
    )
    (net (code "64") (name "USBHS_REFCLK_27MHz") (class "Default")
      (node (ref "R100") (pin "2") (pinfunction "2_2") (pintype "passive"))
    )
    (net (code "65") (name "unconnected-(R101-Pad2)") (class "Default")
      (node (ref "R101") (pin "2") (pinfunction "2_2") (pintype "passive"))
    )
    (net (code "66") (name "unconnected-(U23-IN2-Pad14)") (class "Default")
      (node (ref "U23") (pin "14") (pinfunction "IN2_14") (pintype "input"))
    )
    (net (code "67") (name "unconnected-(U23-IN2B-Pad15)") (class "Default")
      (node (ref "U23") (pin "15") (pinfunction "IN2B_15") (pintype "input"))
    )
    (net (code "68") (name "unconnected-(U23-OUT0B-Pad23)") (class "Default")
      (node (ref "U23") (pin "23") (pinfunction "OUT0B_23") (pintype "output"))
    )
    (net (code "69") (name "unconnected-(U23-OUT4B-Pad37)") (class "Default")
      (node (ref "U23") (pin "37") (pinfunction "OUT4B_37") (pintype "output"))
    )
    (net (code "70") (name "unconnected-(U23-OUT5B-Pad41)") (class "Default")
      (node (ref "U23") (pin "41") (pinfunction "OUT5B_41") (pintype "output"))
    )
    (net (code "71") (name "unconnected-(U23-OUT6B-Pad44)") (class "Default")
      (node (ref "U23") (pin "44") (pinfunction "OUT6B_44") (pintype "output"))
    )
    (net (code "72") (name "unconnected-(U23-OUT9B-Pad58)") (class "Default")
      (node (ref "U23") (pin "58") (pinfunction "OUT9B_58") (pintype "output"))
    )
    (net (code "73") (name "unconnected-(U23-RSVD-Pad20)") (class "Default")
      (node (ref "U23") (pin "20") (pinfunction "RSVD_20") (pintype "passive"))
    )
    (net (code "74") (name "unconnected-(U23-RSVD-Pad21)") (class "Default")
      (node (ref "U23") (pin "21") (pinfunction "RSVD_21") (pintype "passive"))
    )
    (net (code "75") (name "unconnected-(U23-RSVD-Pad55)") (class "Default")
      (node (ref "U23") (pin "55") (pinfunction "RSVD_55") (pintype "passive"))
    )
    (net (code "76") (name "unconnected-(U23-RSVD-Pad56)") (class "Default")
      (node (ref "U23") (pin "56") (pinfunction "RSVD_56") (pintype "passive"))
    )
  )
)
